# ProyectoFinal2.net
KiCad netlist of a schematic drawn in EAGLE
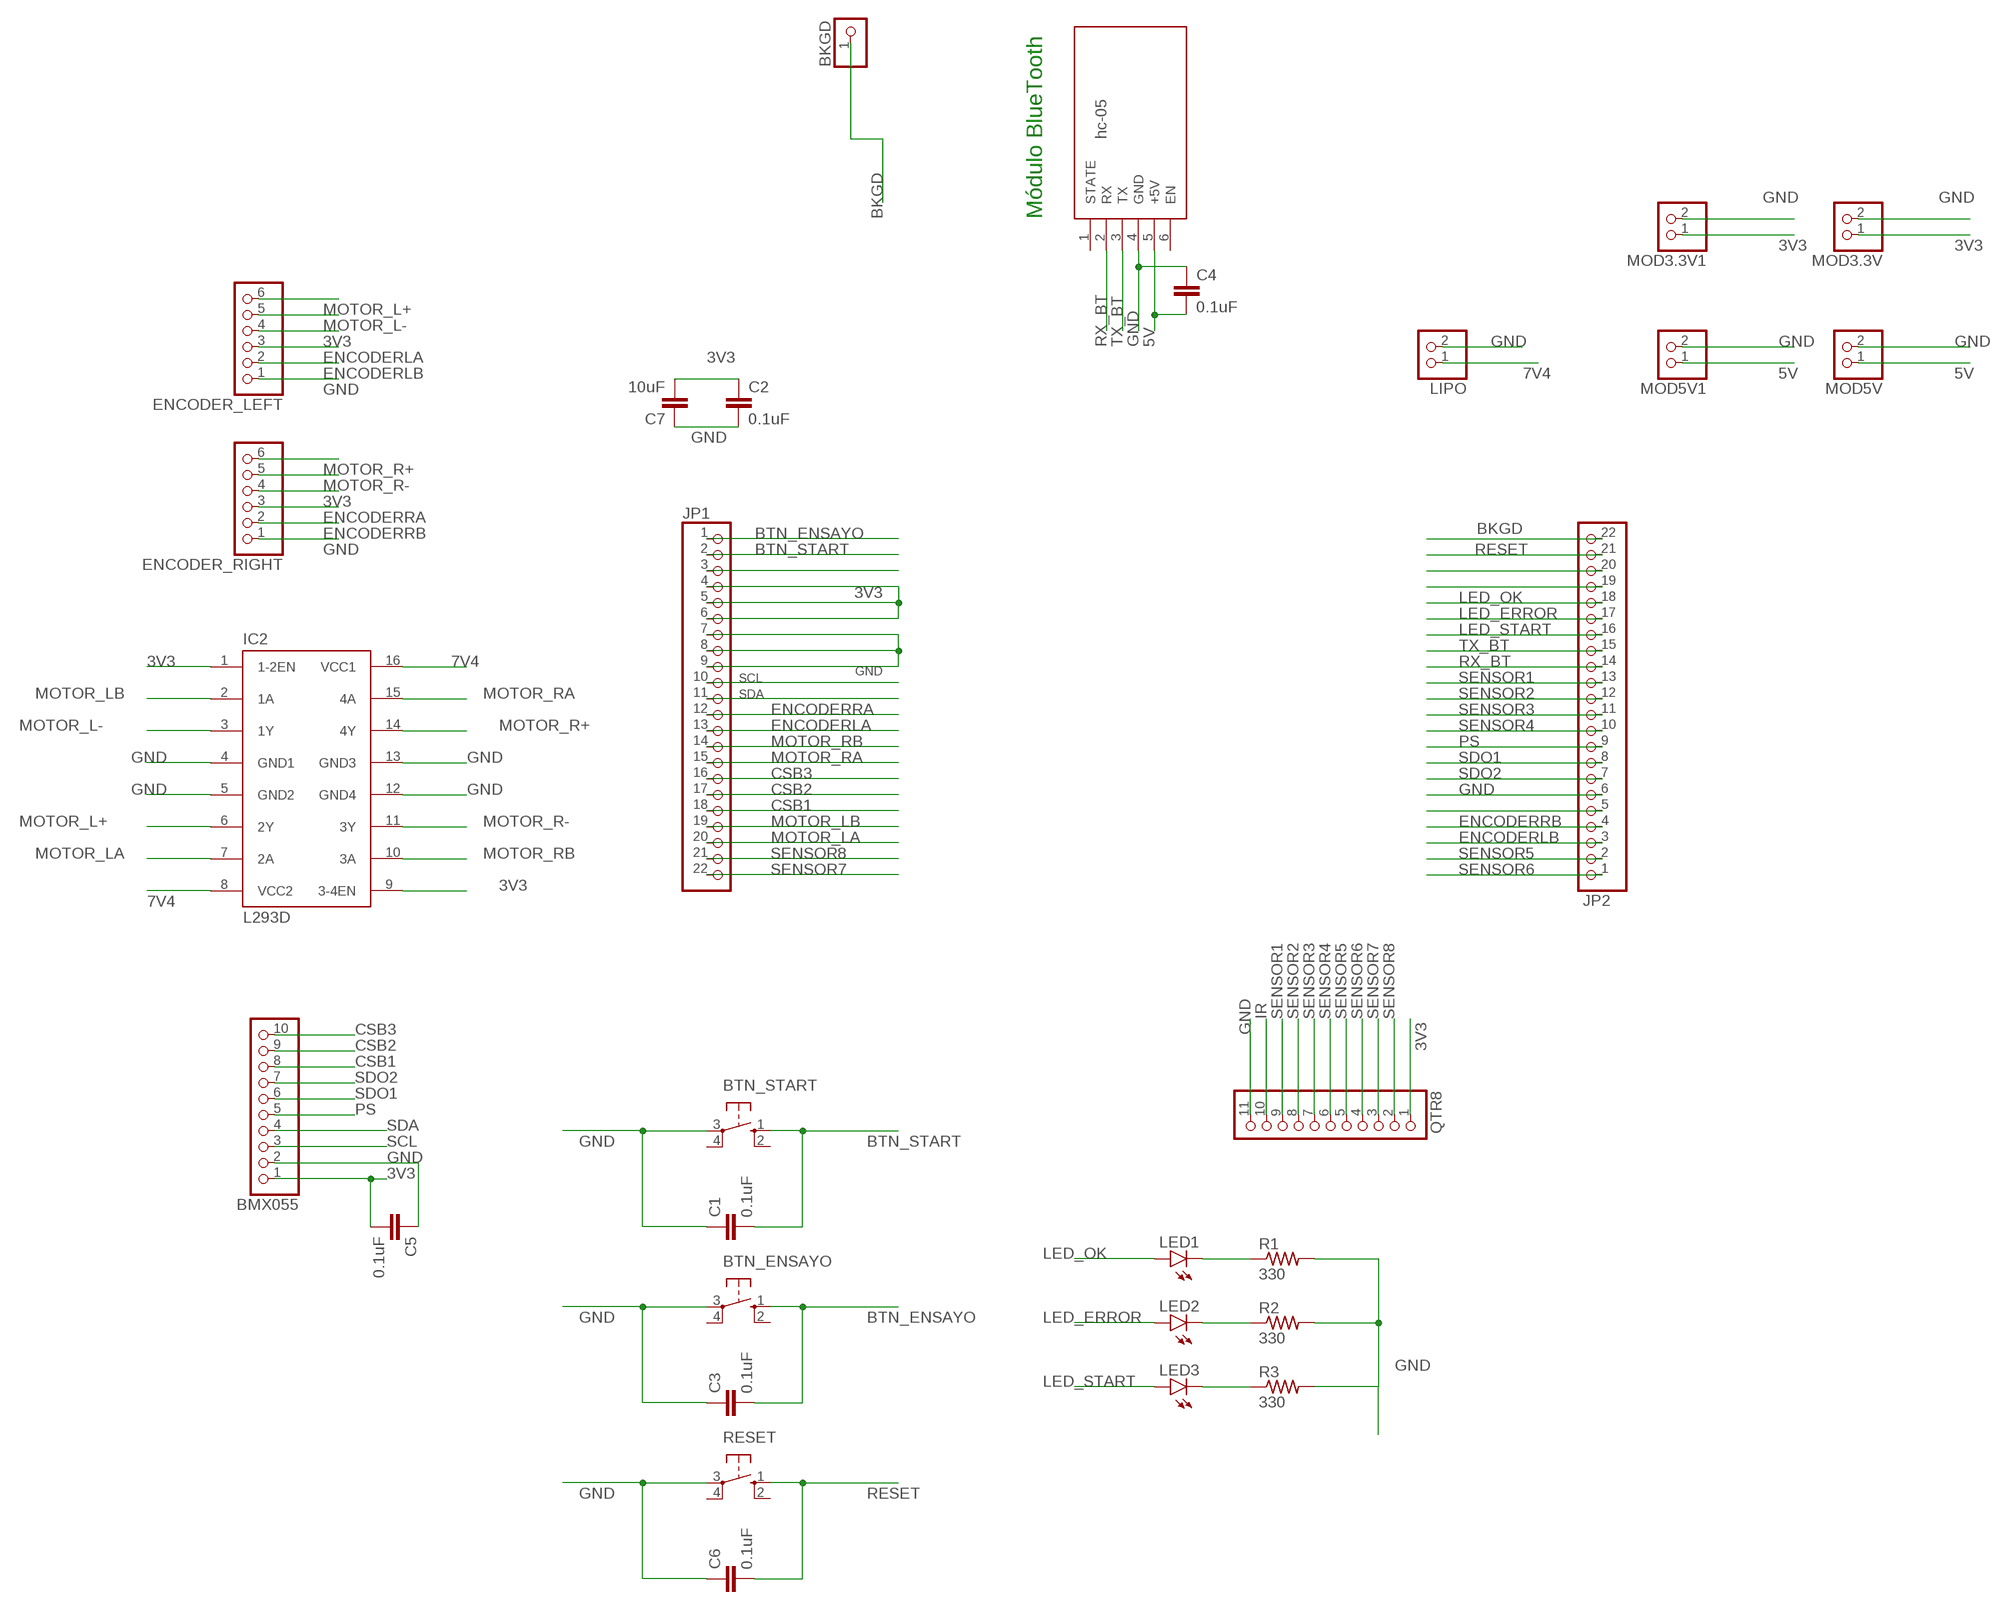
[diagram p0: schematic, sheet 1]

(export (version "E")
  (design (tool "Eeschema 10.0.6"))
  (components
    (comp (ref "BKGD")
      (value "PINHD-1X1")
      (footprint "eagle-import:1X01")
      (libsource (lib "eagle-import") (part "PINHD-1X1"))
    )
    (comp (ref "BLUETOOTH")
      (value "hc-05")
      (footprint "eagle-import:WIRELESS-BLUETOOTH-HC-05")
      (libsource (lib "eagle-import") (part "WIRELESS-BLUETOOTH-HC-05"))
    )
    (comp (ref "BMX055")
      (value "PINHD-1X10")
      (footprint "eagle-import:1X10")
      (libsource (lib "eagle-import") (part "PINHD-1X10"))
    )
    (comp (ref "BTN_ENSAYO")
      (value "10-XX")
      (footprint "eagle-import:B3F-10XX")
      (fields (field (name "MPN") "B3F-1000"))
      (libsource (lib "eagle-import") (part "10-XX"))
    )
    (comp (ref "BTN_START")
      (value "10-XX")
      (footprint "eagle-import:B3F-10XX")
      (fields (field (name "MPN") "B3F-1000"))
      (libsource (lib "eagle-import") (part "10-XX"))
    )
    (comp (ref "C1")
      (value "0.1uF")
      (footprint "eagle-import:C0805K")
      (libsource (lib "eagle-import") (part "C-EUC0805K"))
    )
    (comp (ref "C2")
      (value "0.1uF")
      (footprint "eagle-import:C0805K")
      (libsource (lib "eagle-import") (part "C-EUC0805K"))
    )
    (comp (ref "C3")
      (value "0.1uF")
      (footprint "eagle-import:C0805K")
      (libsource (lib "eagle-import") (part "C-EUC0805K"))
    )
    (comp (ref "C4")
      (value "0.1uF")
      (footprint "eagle-import:C0805K")
      (libsource (lib "eagle-import") (part "C-EUC0805K"))
    )
    (comp (ref "C5")
      (value "0.1uF")
      (footprint "eagle-import:C0805K")
      (libsource (lib "eagle-import") (part "C-EUC0805K"))
    )
    (comp (ref "C6")
      (value "0.1uF")
      (footprint "eagle-import:C0805K")
      (libsource (lib "eagle-import") (part "C-EUC0805K"))
    )
    (comp (ref "C7")
      (value "10uF")
      (footprint "eagle-import:C1206K")
      (libsource (lib "eagle-import") (part "C-EUC1206K"))
    )
    (comp (ref "ENCODER_LEFT")
      (value "PINHD-1X6")
      (footprint "eagle-import:1X06")
      (libsource (lib "eagle-import") (part "PINHD-1X6"))
    )
    (comp (ref "ENCODER_RIGHT")
      (value "PINHD-1X6")
      (footprint "eagle-import:1X06")
      (libsource (lib "eagle-import") (part "PINHD-1X6"))
    )
    (comp (ref "IC2")
      (value "L293D")
      (footprint "eagle-import:DIL16")
      (libsource (lib "eagle-import") (part "L293D"))
    )
    (comp (ref "JP1")
      (value "PINHD-1X22")
      (footprint "eagle-import:1X22")
      (libsource (lib "eagle-import") (part "PINHD-1X22"))
    )
    (comp (ref "JP2")
      (value "PINHD-1X22")
      (footprint "eagle-import:1X22")
      (libsource (lib "eagle-import") (part "PINHD-1X22"))
    )
    (comp (ref "LED1")
      (value "LED5MM")
      (footprint "eagle-import:LED5MM")
      (libsource (lib "eagle-import") (part "LED5MM"))
    )
    (comp (ref "LED2")
      (value "LED5MM")
      (footprint "eagle-import:LED5MM")
      (libsource (lib "eagle-import") (part "LED5MM"))
    )
    (comp (ref "LED3")
      (value "LED5MM")
      (footprint "eagle-import:LED5MM")
      (libsource (lib "eagle-import") (part "LED5MM"))
    )
    (comp (ref "LIPO")
      (value "PINHD-1X2")
      (footprint "eagle-import:1X02")
      (libsource (lib "eagle-import") (part "PINHD-1X2"))
    )
    (comp (ref "MOD3.3V")
      (value "PINHD-1X2")
      (footprint "eagle-import:1X02")
      (libsource (lib "eagle-import") (part "PINHD-1X2"))
    )
    (comp (ref "MOD3.3V1")
      (value "PINHD-1X2")
      (footprint "eagle-import:1X02")
      (libsource (lib "eagle-import") (part "PINHD-1X2"))
    )
    (comp (ref "MOD5V")
      (value "PINHD-1X2")
      (footprint "eagle-import:1X02")
      (libsource (lib "eagle-import") (part "PINHD-1X2"))
    )
    (comp (ref "MOD5V1")
      (value "PINHD-1X2")
      (footprint "eagle-import:1X02")
      (libsource (lib "eagle-import") (part "PINHD-1X2"))
    )
    (comp (ref "QTR8")
      (value "PINHD-1X11")
      (footprint "eagle-import:1X11")
      (libsource (lib "eagle-import") (part "PINHD-1X11"))
    )
    (comp (ref "R1")
      (value "330")
      (footprint "eagle-import:R0805")
      (libsource (lib "eagle-import") (part "R-US_R0805"))
    )
    (comp (ref "R2")
      (value "330")
      (footprint "eagle-import:R0805")
      (libsource (lib "eagle-import") (part "R-US_R0805"))
    )
    (comp (ref "R3")
      (value "330")
      (footprint "eagle-import:R0805")
      (libsource (lib "eagle-import") (part "R-US_R0805"))
    )
    (comp (ref "RESET")
      (value "10-XX")
      (footprint "eagle-import:B3F-10XX")
      (fields (field (name "MPN") "B3F-1000"))
      (libsource (lib "eagle-import") (part "10-XX"))
    )
  )
  (nets
    (net (code "1") (name "/3V3") (class "Default")
      (node (ref "BMX055") (pin "1") (pinfunction "1_1") (pintype "passive"))
      (node (ref "C2") (pin "1") (pinfunction "1_1") (pintype "passive"))
      (node (ref "C5") (pin "2") (pinfunction "2_2") (pintype "passive"))
      (node (ref "C7") (pin "2") (pinfunction "2_2") (pintype "passive"))
      (node (ref "ENCODER_LEFT") (pin "4") (pinfunction "4_4") (pintype "passive"))
      (node (ref "ENCODER_RIGHT") (pin "4") (pinfunction "4_4") (pintype "passive"))
      (node (ref "IC2") (pin "1") (pinfunction "1-2EN_1") (pintype "input"))
      (node (ref "IC2") (pin "9") (pinfunction "3-4EN_9") (pintype "input"))
      (node (ref "JP1") (pin "4") (pinfunction "4_4") (pintype "passive"))
      (node (ref "JP1") (pin "5") (pinfunction "5_5") (pintype "passive"))
      (node (ref "JP1") (pin "6") (pinfunction "6_6") (pintype "passive"))
      (node (ref "MOD3.3V") (pin "1") (pinfunction "1_1") (pintype "passive"))
      (node (ref "MOD3.3V1") (pin "1") (pinfunction "1_1") (pintype "passive"))
      (node (ref "QTR8") (pin "1") (pinfunction "1_1") (pintype "passive"))
    )
    (net (code "2") (name "/5V") (class "Default")
      (node (ref "BLUETOOTH") (pin "5") (pinfunction "+5V_5") (pintype "power_in"))
      (node (ref "C4") (pin "2") (pinfunction "2_2") (pintype "passive"))
      (node (ref "MOD5V") (pin "1") (pinfunction "1_1") (pintype "passive"))
      (node (ref "MOD5V1") (pin "1") (pinfunction "1_1") (pintype "passive"))
    )
    (net (code "3") (name "/7V4") (class "Default")
      (node (ref "IC2") (pin "16") (pinfunction "VCC1_16") (pintype "power_in"))
      (node (ref "IC2") (pin "8") (pinfunction "VCC2_8") (pintype "power_in"))
      (node (ref "LIPO") (pin "1") (pinfunction "1_1") (pintype "passive"))
    )
    (net (code "4") (name "/BKGD") (class "Default")
      (node (ref "BKGD") (pin "1") (pinfunction "1_1") (pintype "passive"))
      (node (ref "JP2") (pin "22") (pinfunction "22_22") (pintype "passive"))
    )
    (net (code "5") (name "/BTN_ENSAYO") (class "Default")
      (node (ref "BTN_ENSAYO") (pin "1") (pinfunction "S_1") (pintype "passive"))
      (node (ref "C3") (pin "2") (pinfunction "2_2") (pintype "passive"))
      (node (ref "JP1") (pin "1") (pinfunction "1_1") (pintype "passive"))
    )
    (net (code "6") (name "/BTN_START") (class "Default")
      (node (ref "BTN_START") (pin "1") (pinfunction "S_1") (pintype "passive"))
      (node (ref "C1") (pin "2") (pinfunction "2_2") (pintype "passive"))
      (node (ref "JP1") (pin "2") (pinfunction "2_2") (pintype "passive"))
    )
    (net (code "7") (name "/CSB1") (class "Default")
      (node (ref "BMX055") (pin "8") (pinfunction "8_8") (pintype "passive"))
      (node (ref "JP1") (pin "18") (pinfunction "18_18") (pintype "passive"))
    )
    (net (code "8") (name "/CSB2") (class "Default")
      (node (ref "BMX055") (pin "9") (pinfunction "9_9") (pintype "passive"))
      (node (ref "JP1") (pin "17") (pinfunction "17_17") (pintype "passive"))
    )
    (net (code "9") (name "/CSB3") (class "Default")
      (node (ref "BMX055") (pin "10") (pinfunction "10_10") (pintype "passive"))
      (node (ref "JP1") (pin "16") (pinfunction "16_16") (pintype "passive"))
    )
    (net (code "10") (name "/ENCODERLA") (class "Default")
      (node (ref "ENCODER_LEFT") (pin "3") (pinfunction "3_3") (pintype "passive"))
      (node (ref "JP1") (pin "13") (pinfunction "13_13") (pintype "passive"))
    )
    (net (code "11") (name "/ENCODERLB") (class "Default")
      (node (ref "ENCODER_LEFT") (pin "2") (pinfunction "2_2") (pintype "passive"))
      (node (ref "JP2") (pin "3") (pinfunction "3_3") (pintype "passive"))
    )
    (net (code "12") (name "/ENCODERRA") (class "Default")
      (node (ref "ENCODER_RIGHT") (pin "3") (pinfunction "3_3") (pintype "passive"))
      (node (ref "JP1") (pin "12") (pinfunction "12_12") (pintype "passive"))
    )
    (net (code "13") (name "/ENCODERRB") (class "Default")
      (node (ref "ENCODER_RIGHT") (pin "2") (pinfunction "2_2") (pintype "passive"))
      (node (ref "JP2") (pin "4") (pinfunction "4_4") (pintype "passive"))
    )
    (net (code "14") (name "/GND") (class "Default")
      (node (ref "BLUETOOTH") (pin "4") (pinfunction "GND_4") (pintype "power_in"))
      (node (ref "BMX055") (pin "2") (pinfunction "2_2") (pintype "passive"))
      (node (ref "BTN_ENSAYO") (pin "3") (pinfunction "P_3") (pintype "passive"))
      (node (ref "BTN_START") (pin "3") (pinfunction "P_3") (pintype "passive"))
      (node (ref "C1") (pin "1") (pinfunction "1_1") (pintype "passive"))
      (node (ref "C2") (pin "2") (pinfunction "2_2") (pintype "passive"))
      (node (ref "C3") (pin "1") (pinfunction "1_1") (pintype "passive"))
      (node (ref "C4") (pin "1") (pinfunction "1_1") (pintype "passive"))
      (node (ref "C5") (pin "1") (pinfunction "1_1") (pintype "passive"))
      (node (ref "C6") (pin "1") (pinfunction "1_1") (pintype "passive"))
      (node (ref "C7") (pin "1") (pinfunction "1_1") (pintype "passive"))
      (node (ref "ENCODER_LEFT") (pin "1") (pinfunction "1_1") (pintype "passive"))
      (node (ref "ENCODER_RIGHT") (pin "1") (pinfunction "1_1") (pintype "passive"))
      (node (ref "IC2") (pin "12") (pinfunction "GND4_12") (pintype "power_in"))
      (node (ref "IC2") (pin "13") (pinfunction "GND3_13") (pintype "power_in"))
      (node (ref "IC2") (pin "4") (pinfunction "GND1_4") (pintype "power_in"))
      (node (ref "IC2") (pin "5") (pinfunction "GND2_5") (pintype "power_in"))
      (node (ref "JP1") (pin "7") (pinfunction "7_7") (pintype "passive"))
      (node (ref "JP1") (pin "8") (pinfunction "8_8") (pintype "passive"))
      (node (ref "JP1") (pin "9") (pinfunction "9_9") (pintype "passive"))
      (node (ref "JP2") (pin "6") (pinfunction "6_6") (pintype "passive"))
      (node (ref "LIPO") (pin "2") (pinfunction "2_2") (pintype "passive"))
      (node (ref "MOD3.3V") (pin "2") (pinfunction "2_2") (pintype "passive"))
      (node (ref "MOD3.3V1") (pin "2") (pinfunction "2_2") (pintype "passive"))
      (node (ref "MOD5V") (pin "2") (pinfunction "2_2") (pintype "passive"))
      (node (ref "MOD5V1") (pin "2") (pinfunction "2_2") (pintype "passive"))
      (node (ref "QTR8") (pin "11") (pinfunction "11_11") (pintype "passive"))
      (node (ref "R1") (pin "2") (pinfunction "2_2") (pintype "passive"))
      (node (ref "R2") (pin "2") (pinfunction "2_2") (pintype "passive"))
      (node (ref "R3") (pin "2") (pinfunction "2_2") (pintype "passive"))
      (node (ref "RESET") (pin "3") (pinfunction "P_3") (pintype "passive"))
    )
    (net (code "15") (name "/IR") (class "Default")
      (node (ref "QTR8") (pin "10") (pinfunction "10_10") (pintype "passive"))
    )
    (net (code "16") (name "/LED_ERROR") (class "Default")
      (node (ref "JP2") (pin "17") (pinfunction "17_17") (pintype "passive"))
      (node (ref "LED2") (pin "A") (pinfunction "A_A") (pintype "passive"))
    )
    (net (code "17") (name "/LED_OK") (class "Default")
      (node (ref "JP2") (pin "18") (pinfunction "18_18") (pintype "passive"))
      (node (ref "LED1") (pin "A") (pinfunction "A_A") (pintype "passive"))
    )
    (net (code "18") (name "/LED_START") (class "Default")
      (node (ref "JP2") (pin "16") (pinfunction "16_16") (pintype "passive"))
      (node (ref "LED3") (pin "A") (pinfunction "A_A") (pintype "passive"))
    )
    (net (code "19") (name "/MOTOR_L+") (class "Default")
      (node (ref "ENCODER_LEFT") (pin "6") (pinfunction "6_6") (pintype "passive"))
      (node (ref "IC2") (pin "6") (pinfunction "2Y_6") (pintype "output"))
    )
    (net (code "20") (name "/MOTOR_L-") (class "Default")
      (node (ref "ENCODER_LEFT") (pin "5") (pinfunction "5_5") (pintype "passive"))
      (node (ref "IC2") (pin "3") (pinfunction "1Y_3") (pintype "output"))
    )
    (net (code "21") (name "/MOTOR_LA") (class "Default")
      (node (ref "IC2") (pin "7") (pinfunction "2A_7") (pintype "input"))
      (node (ref "JP1") (pin "20") (pinfunction "20_20") (pintype "passive"))
    )
    (net (code "22") (name "/MOTOR_LB") (class "Default")
      (node (ref "IC2") (pin "2") (pinfunction "1A_2") (pintype "input"))
      (node (ref "JP1") (pin "19") (pinfunction "19_19") (pintype "passive"))
    )
    (net (code "23") (name "/MOTOR_R+") (class "Default")
      (node (ref "ENCODER_RIGHT") (pin "6") (pinfunction "6_6") (pintype "passive"))
      (node (ref "IC2") (pin "14") (pinfunction "4Y_14") (pintype "output"))
    )
    (net (code "24") (name "/MOTOR_R-") (class "Default")
      (node (ref "ENCODER_RIGHT") (pin "5") (pinfunction "5_5") (pintype "passive"))
      (node (ref "IC2") (pin "11") (pinfunction "3Y_11") (pintype "output"))
    )
    (net (code "25") (name "/MOTOR_RA") (class "Default")
      (node (ref "IC2") (pin "15") (pinfunction "4A_15") (pintype "input"))
      (node (ref "JP1") (pin "15") (pinfunction "15_15") (pintype "passive"))
    )
    (net (code "26") (name "/MOTOR_RB") (class "Default")
      (node (ref "IC2") (pin "10") (pinfunction "3A_10") (pintype "input"))
      (node (ref "JP1") (pin "14") (pinfunction "14_14") (pintype "passive"))
    )
    (net (code "27") (name "/PS") (class "Default")
      (node (ref "BMX055") (pin "5") (pinfunction "5_5") (pintype "passive"))
      (node (ref "JP2") (pin "9") (pinfunction "9_9") (pintype "passive"))
    )
    (net (code "28") (name "/RESET") (class "Default")
      (node (ref "C6") (pin "2") (pinfunction "2_2") (pintype "passive"))
      (node (ref "JP2") (pin "21") (pinfunction "21_21") (pintype "passive"))
      (node (ref "RESET") (pin "1") (pinfunction "S_1") (pintype "passive"))
    )
    (net (code "29") (name "/RX_BT") (class "Default")
      (node (ref "BLUETOOTH") (pin "2") (pinfunction "RX_2") (pintype "bidirectional"))
      (node (ref "JP2") (pin "14") (pinfunction "14_14") (pintype "passive"))
    )
    (net (code "30") (name "/SCL") (class "Default")
      (node (ref "BMX055") (pin "3") (pinfunction "3_3") (pintype "passive"))
      (node (ref "JP1") (pin "10") (pinfunction "10_10") (pintype "passive"))
    )
    (net (code "31") (name "/SDA") (class "Default")
      (node (ref "BMX055") (pin "4") (pinfunction "4_4") (pintype "passive"))
      (node (ref "JP1") (pin "11") (pinfunction "11_11") (pintype "passive"))
    )
    (net (code "32") (name "/SDO1") (class "Default")
      (node (ref "BMX055") (pin "6") (pinfunction "6_6") (pintype "passive"))
      (node (ref "JP2") (pin "8") (pinfunction "8_8") (pintype "passive"))
    )
    (net (code "33") (name "/SDO2") (class "Default")
      (node (ref "BMX055") (pin "7") (pinfunction "7_7") (pintype "passive"))
      (node (ref "JP2") (pin "7") (pinfunction "7_7") (pintype "passive"))
    )
    (net (code "34") (name "/SENSOR1") (class "Default")
      (node (ref "JP2") (pin "13") (pinfunction "13_13") (pintype "passive"))
      (node (ref "QTR8") (pin "9") (pinfunction "9_9") (pintype "passive"))
    )
    (net (code "35") (name "/SENSOR2") (class "Default")
      (node (ref "JP2") (pin "12") (pinfunction "12_12") (pintype "passive"))
      (node (ref "QTR8") (pin "8") (pinfunction "8_8") (pintype "passive"))
    )
    (net (code "36") (name "/SENSOR3") (class "Default")
      (node (ref "JP2") (pin "11") (pinfunction "11_11") (pintype "passive"))
      (node (ref "QTR8") (pin "7") (pinfunction "7_7") (pintype "passive"))
    )
    (net (code "37") (name "/SENSOR4") (class "Default")
      (node (ref "JP2") (pin "10") (pinfunction "10_10") (pintype "passive"))
      (node (ref "QTR8") (pin "6") (pinfunction "6_6") (pintype "passive"))
    )
    (net (code "38") (name "/SENSOR5") (class "Default")
      (node (ref "JP2") (pin "2") (pinfunction "2_2") (pintype "passive"))
      (node (ref "QTR8") (pin "5") (pinfunction "5_5") (pintype "passive"))
    )
    (net (code "39") (name "/SENSOR6") (class "Default")
      (node (ref "JP2") (pin "1") (pinfunction "1_1") (pintype "passive"))
      (node (ref "QTR8") (pin "4") (pinfunction "4_4") (pintype "passive"))
    )
    (net (code "40") (name "/SENSOR7") (class "Default")
      (node (ref "JP1") (pin "22") (pinfunction "22_22") (pintype "passive"))
      (node (ref "QTR8") (pin "3") (pinfunction "3_3") (pintype "passive"))
    )
    (net (code "41") (name "/SENSOR8") (class "Default")
      (node (ref "JP1") (pin "21") (pinfunction "21_21") (pintype "passive"))
      (node (ref "QTR8") (pin "2") (pinfunction "2_2") (pintype "passive"))
    )
    (net (code "42") (name "/TX_BT") (class "Default")
      (node (ref "BLUETOOTH") (pin "3") (pinfunction "TX_3") (pintype "bidirectional"))
      (node (ref "JP2") (pin "15") (pinfunction "15_15") (pintype "passive"))
    )
    (net (code "43") (name "Net-(LED1-C)") (class "Default")
      (node (ref "LED1") (pin "K") (pinfunction "C_K") (pintype "passive"))
      (node (ref "R1") (pin "1") (pinfunction "1_1") (pintype "passive"))
    )
    (net (code "44") (name "Net-(LED2-C)") (class "Default")
      (node (ref "LED2") (pin "K") (pinfunction "C_K") (pintype "passive"))
      (node (ref "R2") (pin "1") (pinfunction "1_1") (pintype "passive"))
    )
    (net (code "45") (name "Net-(LED3-C)") (class "Default")
      (node (ref "LED3") (pin "K") (pinfunction "C_K") (pintype "passive"))
      (node (ref "R3") (pin "1") (pinfunction "1_1") (pintype "passive"))
    )
    (net (code "46") (name "unconnected-(BLUETOOTH-EN-Pad6)") (class "Default")
      (node (ref "BLUETOOTH") (pin "6") (pinfunction "EN_6") (pintype "bidirectional"))
    )
    (net (code "47") (name "unconnected-(BLUETOOTH-STATE-Pad1)") (class "Default")
      (node (ref "BLUETOOTH") (pin "1") (pinfunction "STATE_1") (pintype "bidirectional"))
    )
    (net (code "48") (name "unconnected-(BTN_ENSAYO-P1-Pad4)") (class "Default")
      (node (ref "BTN_ENSAYO") (pin "4") (pinfunction "P1_4") (pintype "passive"))
    )
    (net (code "49") (name "unconnected-(BTN_ENSAYO-S1-Pad2)") (class "Default")
      (node (ref "BTN_ENSAYO") (pin "2") (pinfunction "S1_2") (pintype "passive"))
    )
    (net (code "50") (name "unconnected-(BTN_START-P1-Pad4)") (class "Default")
      (node (ref "BTN_START") (pin "4") (pinfunction "P1_4") (pintype "passive"))
    )
    (net (code "51") (name "unconnected-(BTN_START-S1-Pad2)") (class "Default")
      (node (ref "BTN_START") (pin "2") (pinfunction "S1_2") (pintype "passive"))
    )
    (net (code "52") (name "unconnected-(JP1-Pad3)") (class "Default")
      (node (ref "JP1") (pin "3") (pinfunction "3_3") (pintype "passive"))
    )
    (net (code "53") (name "unconnected-(JP2-Pad5)") (class "Default")
      (node (ref "JP2") (pin "5") (pinfunction "5_5") (pintype "passive"))
    )
    (net (code "54") (name "unconnected-(JP2-Pad19)") (class "Default")
      (node (ref "JP2") (pin "19") (pinfunction "19_19") (pintype "passive"))
    )
    (net (code "55") (name "unconnected-(JP2-Pad20)") (class "Default")
      (node (ref "JP2") (pin "20") (pinfunction "20_20") (pintype "passive"))
    )
    (net (code "56") (name "unconnected-(RESET-P1-Pad4)") (class "Default")
      (node (ref "RESET") (pin "4") (pinfunction "P1_4") (pintype "passive"))
    )
    (net (code "57") (name "unconnected-(RESET-S1-Pad2)") (class "Default")
      (node (ref "RESET") (pin "2") (pinfunction "S1_2") (pintype "passive"))
    )
  )
)
